# Black_PSI_Backpack.net
KiCad netlist of a schematic drawn in EAGLE
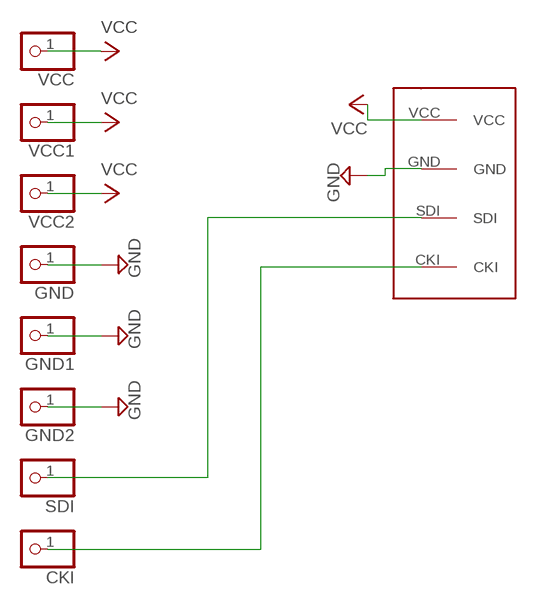
[diagram p0: schematic, sheet 1]

(export (version "E")
  (design (tool "Eeschema 10.0.6"))
  (components
    (comp (ref "CKI")
      (value "PINHD-1X1")
      (footprint "eagle-import:1X01")
      (libsource (lib "eagle-import") (part "PINHD-1X1"))
    )
    (comp (ref "GND")
      (value "PINHD-1X1")
      (footprint "eagle-import:1X01")
      (libsource (lib "eagle-import") (part "PINHD-1X1"))
    )
    (comp (ref "GND1")
      (value "PINHD-1X1")
      (footprint "eagle-import:1X01")
      (libsource (lib "eagle-import") (part "PINHD-1X1"))
    )
    (comp (ref "GND2")
      (value "PINHD-1X1")
      (footprint "eagle-import:1X01")
      (libsource (lib "eagle-import") (part "PINHD-1X1"))
    )
    (comp (ref "SDI")
      (value "PINHD-1X1")
      (footprint "eagle-import:1X01")
      (libsource (lib "eagle-import") (part "PINHD-1X1"))
    )
    (comp (ref "U$1")
      (value "0393570004WIRE-TO-BOARD")
      (footprint "eagle-import:0393570004WIRE-TO-BOARD")
      (libsource (lib "eagle-import") (part "0393570004WIRE-TO-BOARD"))
    )
    (comp (ref "VCC")
      (value "PINHD-1X1")
      (footprint "eagle-import:1X01")
      (libsource (lib "eagle-import") (part "PINHD-1X1"))
    )
    (comp (ref "VCC1")
      (value "PINHD-1X1")
      (footprint "eagle-import:1X01")
      (libsource (lib "eagle-import") (part "PINHD-1X1"))
    )
    (comp (ref "VCC2")
      (value "PINHD-1X1")
      (footprint "eagle-import:1X01")
      (libsource (lib "eagle-import") (part "PINHD-1X1"))
    )
  )
  (nets
    (net (code "1") (name "GND") (class "Default")
      (node (ref "GND") (pin "1") (pinfunction "1_1") (pintype "passive"))
      (node (ref "GND1") (pin "1") (pinfunction "1_1") (pintype "passive"))
      (node (ref "GND2") (pin "1") (pinfunction "1_1") (pintype "passive"))
      (node (ref "U$1") (pin "GND") (pinfunction "GND_GND") (pintype "bidirectional"))
    )
    (net (code "2") (name "Net-(CKI-Pad1)") (class "Default")
      (node (ref "CKI") (pin "1") (pinfunction "1_1") (pintype "passive"))
      (node (ref "U$1") (pin "CKI") (pinfunction "CKI_CKI") (pintype "bidirectional"))
    )
    (net (code "3") (name "Net-(SDI-Pad1)") (class "Default")
      (node (ref "SDI") (pin "1") (pinfunction "1_1") (pintype "passive"))
      (node (ref "U$1") (pin "SDI") (pinfunction "SDI_SDI") (pintype "bidirectional"))
    )
    (net (code "4") (name "VCC") (class "Default")
      (node (ref "U$1") (pin "VCC") (pinfunction "VCC_VCC") (pintype "bidirectional"))
      (node (ref "VCC") (pin "1") (pinfunction "1_1") (pintype "passive"))
      (node (ref "VCC1") (pin "1") (pinfunction "1_1") (pintype "passive"))
      (node (ref "VCC2") (pin "1") (pinfunction "1_1") (pintype "passive"))
    )
  )
)
